# Sheet3.net
KiCad netlist of a schematic drawn in Altium Designer
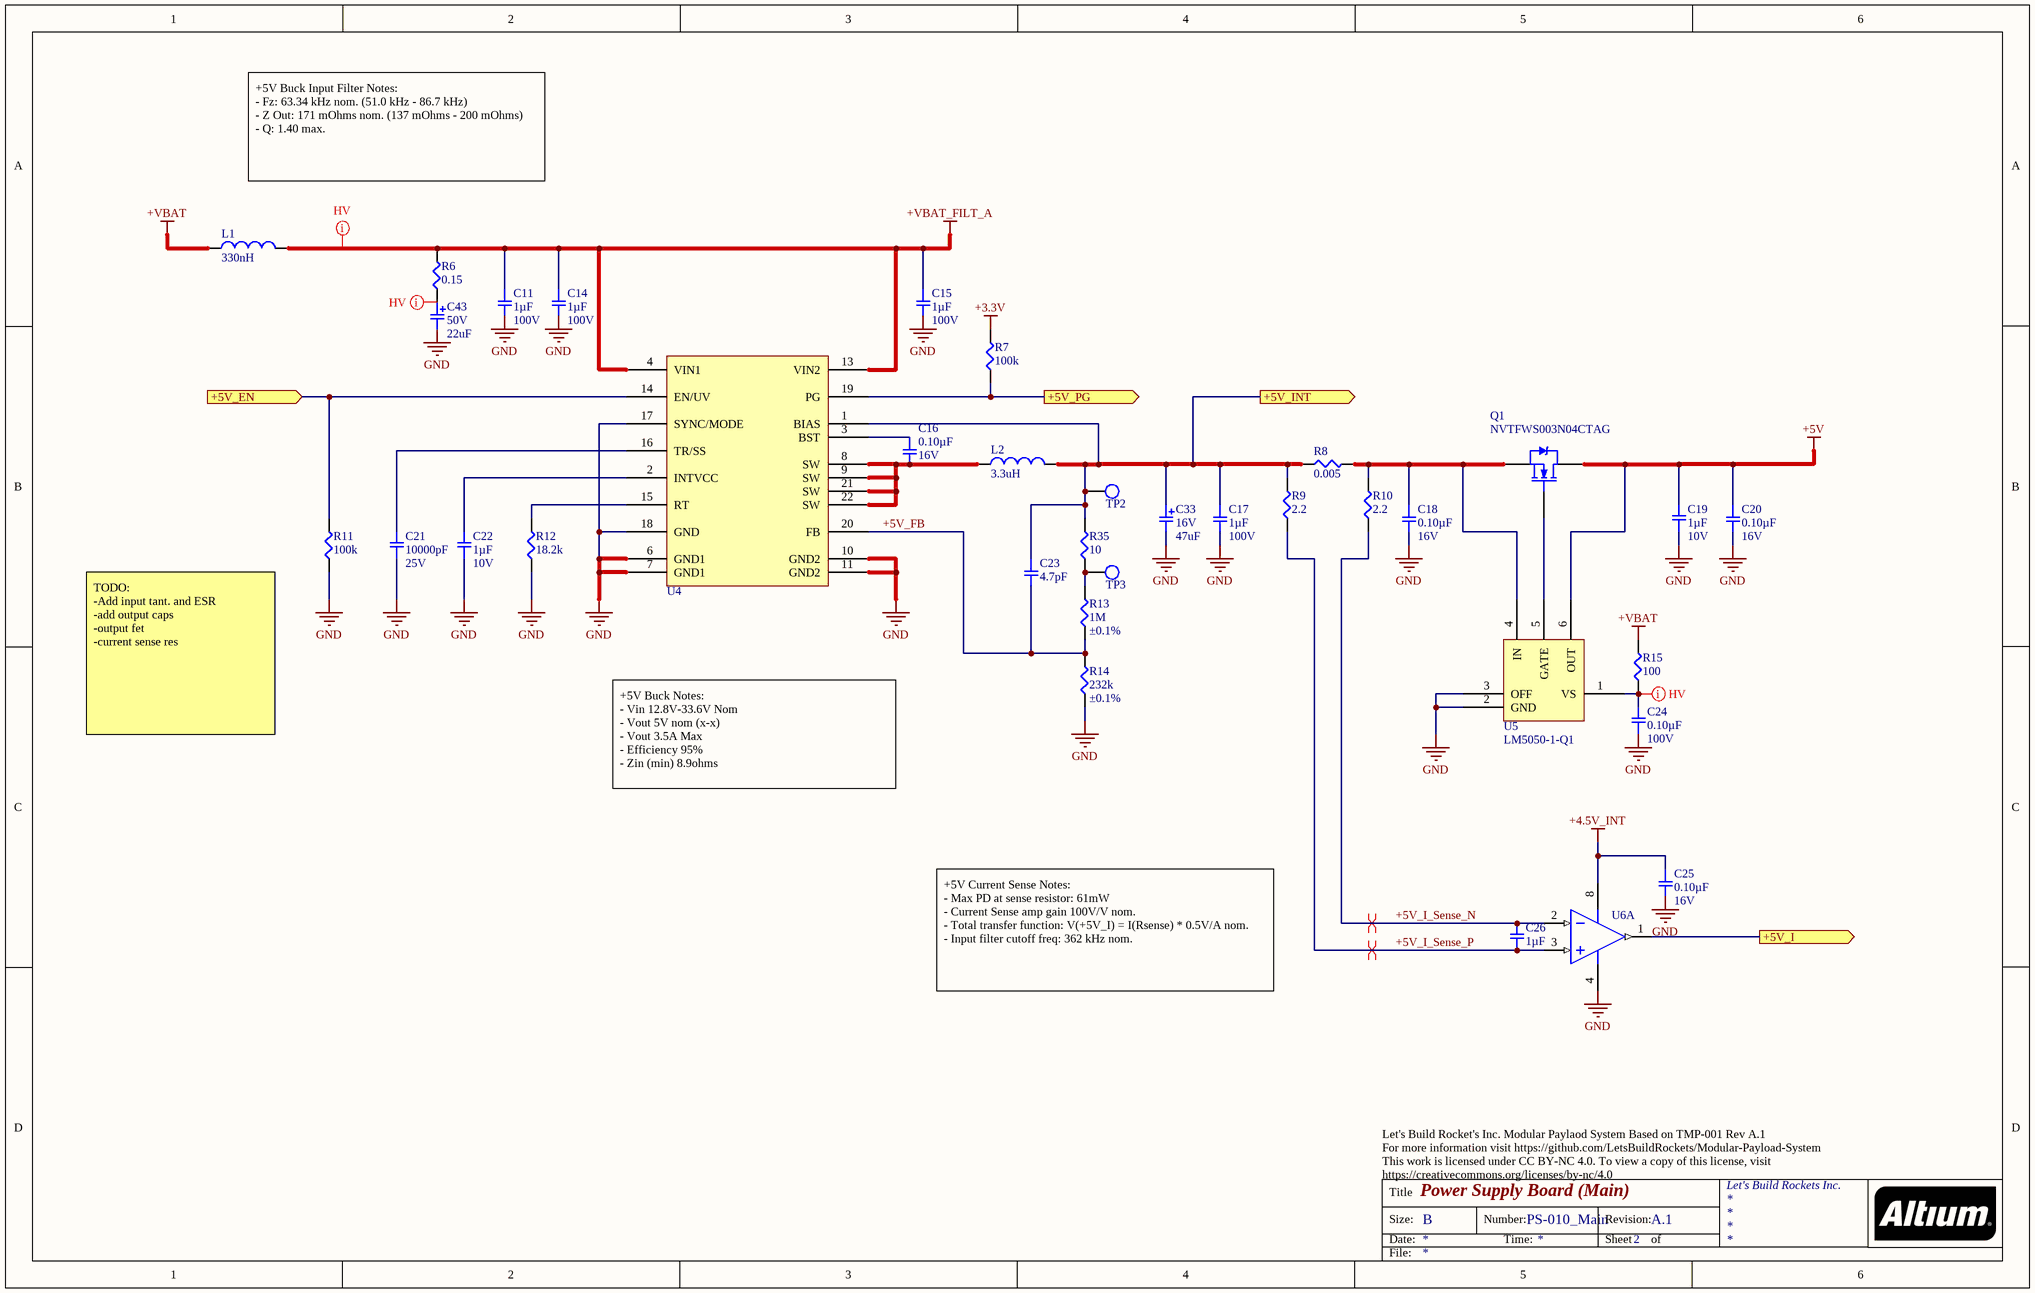
[diagram p0: Sheet3.SchDoc]

(export (version "E")
  (design (tool "Eeschema 10.0.6"))
  (components
    (comp (ref "C11")
      (value "1µF")
      (footprint "SMD-0805C")
      (description "CAP CER 1UF 100V X7S 0805")
      (fields
        (field (name "DIGI-KEY PART NUMBER") "490-10918-1-ND")
        (field (name "PART NUMBER") "GRJ21BC72A105KE11L")
        (field (name "VOLTAGE") "100V")
      )
      (libsource (lib "capacitor_murata_0805") (part "GRJ21BC72A105KE11L"))
    )
    (comp (ref "C14")
      (value "1µF")
      (footprint "SMD-0805C")
      (description "CAP CER 1UF 100V X7S 0805")
      (fields
        (field (name "DIGI-KEY PART NUMBER") "490-10918-1-ND")
        (field (name "PART NUMBER") "GRJ21BC72A105KE11L")
        (field (name "VOLTAGE") "100V")
      )
      (libsource (lib "capacitor_murata_0805") (part "GRJ21BC72A105KE11L"))
    )
    (comp (ref "C15")
      (value "1µF")
      (footprint "SMD-0805C")
      (description "CAP CER 1UF 100V X7S 0805")
      (fields
        (field (name "DIGI-KEY PART NUMBER") "490-10918-1-ND")
        (field (name "PART NUMBER") "GRJ21BC72A105KE11L")
        (field (name "VOLTAGE") "100V")
      )
      (libsource (lib "capacitor_murata_0805") (part "GRJ21BC72A105KE11L"))
    )
    (comp (ref "C16")
      (value "0.10µF")
      (footprint "SMD-0402C")
      (description "CAP CER 0.1UF 16V X7R 0402")
      (fields
        (field (name "DIGI-KEY PART NUMBER") "490-4759-1-ND")
        (field (name "PART NUMBER") "GCM155R71C104KA55D")
        (field (name "VOLTAGE") "16V")
      )
      (libsource (lib "capacitor_murata_0402") (part "GCM155R71C104KA55D"))
    )
    (comp (ref "C17")
      (value "1µF")
      (footprint "SMD-0805C")
      (description "CAP CER 1UF 100V X7S 0805")
      (fields
        (field (name "DIGI-KEY PART NUMBER") "490-10918-1-ND")
        (field (name "PART NUMBER") "GRJ21BC72A105KE11L")
        (field (name "VOLTAGE") "100V")
      )
      (libsource (lib "capacitor_murata_0805") (part "GRJ21BC72A105KE11L"))
    )
    (comp (ref "C18")
      (value "0.10µF")
      (footprint "SMD-0402C")
      (description "CAP CER 0.1UF 16V X7R 0402")
      (fields
        (field (name "DIGI-KEY PART NUMBER") "490-4759-1-ND")
        (field (name "PART NUMBER") "GCM155R71C104KA55D")
        (field (name "VOLTAGE") "16V")
      )
      (libsource (lib "capacitor_murata_0402") (part "GCM155R71C104KA55D"))
    )
    (comp (ref "C19")
      (value "1µF")
      (footprint "SMD-0402C")
      (description "CAP CER 1UF 10V X7S 0402")
      (fields
        (field (name "DIGI-KEY PART NUMBER") "490-13409-1-ND")
        (field (name "PART NUMBER") "GCM155C71A105KE38D")
        (field (name "VOLTAGE") "10V")
      )
      (libsource (lib "capacitor_murata_0402") (part "GCM155C71A105KE38D"))
    )
    (comp (ref "C20")
      (value "0.10µF")
      (footprint "SMD-0402C")
      (description "CAP CER 0.1UF 16V X7R 0402")
      (fields
        (field (name "DIGI-KEY PART NUMBER") "490-4759-1-ND")
        (field (name "PART NUMBER") "GCM155R71C104KA55D")
        (field (name "VOLTAGE") "16V")
      )
      (libsource (lib "capacitor_murata_0402") (part "GCM155R71C104KA55D"))
    )
    (comp (ref "C21")
      (value "10000pF")
      (footprint "SMD-0402C")
      (description "CAP CER 10000PF 25V X7R 0402")
      (fields
        (field (name "DIGI-KEY PART NUMBER") "490-6043-1-ND")
        (field (name "PART NUMBER") "GCM155R71E103KA37D")
        (field (name "VOLTAGE") "25V")
      )
      (libsource (lib "capacitor_murata_0402") (part "GCM155R71E103KA37D"))
    )
    (comp (ref "C22")
      (value "1µF")
      (footprint "SMD-0402C")
      (description "CAP CER 1UF 10V X7S 0402")
      (fields
        (field (name "DIGI-KEY PART NUMBER") "490-13409-1-ND")
        (field (name "PART NUMBER") "GCM155C71A105KE38D")
        (field (name "VOLTAGE") "10V")
      )
      (libsource (lib "capacitor_murata_0402") (part "GCM155C71A105KE38D"))
    )
    (comp (ref "C23")
      (value "4.7pF")
      (footprint "SMD-0402C")
      (description "CAP CER 4.7PF 50V NP0 0402")
      (fields
        (field (name "DIGI-KEY PART NUMBER") "490-12652-1-ND")
        (field (name "PART NUMBER") "GCM1555C1H4R7CA16D")
      )
      (libsource (lib "capacitor_murata_0402") (part "GCM1555C1H4R7CA16D"))
    )
    (comp (ref "C24")
      (value "0.10µF")
      (footprint "SMD-0603C")
      (description "CAP CER 0.1UF 100V X7R 0603")
      (fields
        (field (name "DIGI-KEY PART NUMBER") "490-3285-1-ND")
        (field (name "PART NUMBER") "GRM188R72A104KA35D")
        (field (name "VOLTAGE") "100V")
      )
      (libsource (lib "capacitor_murata_0603") (part "GRM188R72A104KA35D"))
    )
    (comp (ref "C25")
      (value "0.10µF")
      (footprint "SMD-0402C")
      (description "CAP CER 0.1UF 16V X7R 0402")
      (fields
        (field (name "DIGI-KEY PART NUMBER") "490-4759-1-ND")
        (field (name "PART NUMBER") "GCM155R71C104KA55D")
        (field (name "VOLTAGE") "16V")
      )
      (libsource (lib "capacitor_murata_0402") (part "GCM155R71C104KA55D"))
    )
    (comp (ref "C26")
      (value "1µF")
      (footprint "SMD-0402C")
      (description "CAP CER 1UF 10V X7S 0402")
      (fields
        (field (name "DIGI-KEY PART NUMBER") "490-13409-1-ND")
        (field (name "PART NUMBER") "GCM155C71A105KE38D")
      )
      (libsource (lib "capacitor_murata_0402") (part "GCM155C71A105KE38D"))
    )
    (comp (ref "C33")
      (value "47uF")
      (footprint "KEMET W - CAPMP7343X15N")
      (fields (field (name "VOLTAGE") "16V") (field (name "Comment") "T521W476M016ATE045"))
      (libsource (lib "KEMET") (part "T521W476M016ATE045"))
    )
    (comp (ref "C43")
      (value "22uF")
      (footprint "KEMET D - CAPMP7343X31N")
      (fields (field (name "VOLTAGE") "50V") (field (name "Comment") "T521D226M050ATE090"))
      (libsource (lib "KEMET") (part "T521D226M050ATE090"))
    )
    (comp (ref "L1")
      (value "330nH")
      (footprint "INDM4040X21N (XGL4020)")
      (fields (field (name "Comment") "XGL4020-331ME"))
      (libsource (lib "ModularPayload") (part "XGL4020-331ME"))
    )
    (comp (ref "L2")
      (value "3.3uH")
      (footprint "INDM7050X50N (Wurth)")
      (fields (field (name "TOLERANCE") "20%") (field (name "Comment") "744314330"))
      (libsource (lib "ModularPayload") (part "744314330"))
    )
    (comp (ref "Q1")
      (value "NVTFWS003N04CTAG")
      (footprint "DFN065P305X80-8N")
      (libsource (lib "ModularPayload") (part "NVTFWS003N04CTAG"))
    )
    (comp (ref "R6")
      (value "0.15")
      (footprint "SMD-0603-RES")
      (description "RES SMD 0.15 OHM 5% 1/4W 0603")
      (fields (field (name "PART NUMBER") "ERJ-3BSJR15V") (field (name "DIGI-KEY PART NUMBER") "P17248CT-ND"))
      (libsource (lib "Panasonic_ERJ_0603") (part "ERJ-3BSJR15V"))
    )
    (comp (ref "R7")
      (value "100k")
      (footprint "SMD-0402-RES")
      (description "RES SMD 100K OHM 5% 1/10W 0402")
      (fields (field (name "PART NUMBER") "ERJ-2GEJ104X") (field (name "DIGI-KEY PART NUMBER") "P100KJCT-ND"))
      (libsource (lib "Panasonic_ERJ_0402") (part "ERJ-2GEJ104X"))
    )
    (comp (ref "R8")
      (value "0.005")
      (footprint "SMD-0603-RES")
      (description "RES SMD 0.005 OHM 1% 1/4W 0603")
      (fields
        (field (name "PART NUMBER") "ERJ-3LWFR005V")
        (field (name "DIGI-KEY PART NUMBER") "P19182CT-ND")
      )
      (libsource (lib "Panasonic_ERJ_0603") (part "ERJ-3LWFR005V"))
    )
    (comp (ref "R9")
      (value "2.2")
      (footprint "SMD-0603-RES")
      (description "RES SMD 2.2 OHM 1% 1/10W 0603")
      (fields (field (name "PART NUMBER") "ERJ-3RQF2R2V") (field (name "DIGI-KEY PART NUMBER") "P2.2AJCT-ND"))
      (libsource (lib "Panasonic_ERJ_0603") (part "ERJ-3RQF2R2V"))
    )
    (comp (ref "R10")
      (value "2.2")
      (footprint "SMD-0603-RES")
      (description "RES SMD 2.2 OHM 1% 1/10W 0603")
      (fields (field (name "PART NUMBER") "ERJ-3RQF2R2V") (field (name "DIGI-KEY PART NUMBER") "P2.2AJCT-ND"))
      (libsource (lib "Panasonic_ERJ_0603") (part "ERJ-3RQF2R2V"))
    )
    (comp (ref "R11")
      (value "100k")
      (footprint "SMD-0402-RES")
      (description "RES SMD 100K OHM 5% 1/10W 0402")
      (fields (field (name "PART NUMBER") "ERJ-2GEJ104X") (field (name "DIGI-KEY PART NUMBER") "P100KJCT-ND"))
      (libsource (lib "Panasonic_ERJ_0402") (part "ERJ-2GEJ104X"))
    )
    (comp (ref "R12")
      (value "18.2k")
      (footprint "SMD-0402-RES")
      (description "RES SMD 18.2K OHM 1% 1/10W 0402")
      (fields
        (field (name "PART NUMBER") "ERJ-2RKF1822X")
        (field (name "DIGI-KEY PART NUMBER") "P18.2KLCT-ND")
      )
      (libsource (lib "Panasonic_ERJ_0402") (part "ERJ-2RKF1822X"))
    )
    (comp (ref "R13")
      (value "1M")
      (footprint "SMD-0805-RES")
      (description "RES SMD 1M OHM 0.1% 1/4W 0805")
      (fields
        (field (name "PART NUMBER") "ERJ-PB6B1004V")
        (field (name "DIGI-KEY PART NUMBER") "P20936CT-ND")
        (field (name "TOLERANCE") "±0.1%")
      )
      (libsource (lib "Panasonic_ERJ_0805") (part "ERJ-PB6B1004V"))
    )
    (comp (ref "R14")
      (value "232k")
      (footprint "SMD-0805-RES")
      (description "RES SMD 232k OHM 0.1% 1/4W 0805")
      (fields
        (field (name "PART NUMBER") "ERJ-PB6B2323V")
        (field (name "DIGI-KEY PART NUMBER") "P20861CT-ND")
        (field (name "TOLERANCE") "±0.1%")
      )
      (libsource (lib "Panasonic_ERJ_0805") (part "ERJ-PB6B2323V"))
    )
    (comp (ref "R15")
      (value "100")
      (footprint "SMD-0402-RES")
      (description "RES SMD 100 OHM 5% 1/10W 0402")
      (fields (field (name "PART NUMBER") "ERJ-2GEJ101X") (field (name "DIGI-KEY PART NUMBER") "P100JCT-ND"))
      (libsource (lib "Panasonic_ERJ_0402") (part "ERJ-2GEJ101X"))
    )
    (comp (ref "R35")
      (value "10")
      (footprint "SMD-0402-RES")
      (description "RES SMD 10 OHM 5% 1/10W 0402")
      (fields (field (name "PART NUMBER") "ERJ-2GEJ100X") (field (name "DIGI-KEY PART NUMBER") "P10JCT-ND"))
      (libsource (lib "Panasonic_ERJ_0402") (part "ERJ-2GEJ100X"))
    )
    (comp (ref "TP2") (value "TP") (footprint "TP_SMD_40") (libsource (lib "TP") (part "TP")))
    (comp (ref "TP3") (value "TP") (footprint "TP_SMD_40") (libsource (lib "TP") (part "TP")))
    (comp (ref "U4")
      (value "LT8640")
      (footprint "QFN50P300X400X80_HS-21N (LT8640)")
      (libsource (lib "ModularPayload") (part "LT8640"))
    )
    (comp (ref "U5")
      (value "LM5050-1-Q1")
      (footprint "SOT95P280X110-6N")
      (libsource (lib "ModularPayload") (part "LM5050-1-Q1"))
    )
    (comp (ref "U6")
      (value "INA2180A3IDGKT")
      (footprint "TSOP65P490X110-8N")
      (libsource (lib "ModularPayload") (part "INA2180A3IDGKT"))
    )
  )
  (nets
    (net (code "1") (name "+3.3V") (class "Default")
      (node (ref "R7") (pin "2") (pinfunction "2_2") (pintype "passive"))
    )
    (net (code "2") (name "+4.5V_INT") (class "Default")
      (node (ref "C25") (pin "1") (pinfunction "1_1") (pintype "passive"))
      (node (ref "U6") (pin "8") (pinfunction "VS_8") (pintype "power_in"))
    )
    (net (code "3") (name "+5V") (class "Default")
      (node (ref "C19") (pin "2") (pinfunction "2_2") (pintype "passive"))
      (node (ref "C20") (pin "1") (pinfunction "1_1") (pintype "passive"))
      (node (ref "Q1") (pin "D") (pinfunction "D_D") (pintype "passive"))
      (node (ref "U5") (pin "6") (pinfunction "OUT_6") (pintype "passive"))
    )
    (net (code "4") (name "+VBAT") (class "Default")
      (node (ref "L1") (pin "1") (pinfunction "1_1") (pintype "passive"))
      (node (ref "R15") (pin "2") (pinfunction "2_2") (pintype "passive"))
    )
    (net (code "5") (name "+VBAT_FILT_A") (class "Default")
      (node (ref "C11") (pin "1") (pinfunction "1_1") (pintype "passive"))
      (node (ref "C14") (pin "1") (pinfunction "1_1") (pintype "passive"))
      (node (ref "C15") (pin "1") (pinfunction "1_1") (pintype "passive"))
      (node (ref "L1") (pin "2") (pinfunction "2_2") (pintype "passive"))
      (node (ref "R6") (pin "2") (pinfunction "2_2") (pintype "passive"))
      (node (ref "U4") (pin "13") (pinfunction "VIN2_13") (pintype "passive"))
      (node (ref "U4") (pin "4") (pinfunction "VIN1_4") (pintype "passive"))
    )
    (net (code "6") (name "/+5V_EN") (class "Default")
      (node (ref "R11") (pin "2") (pinfunction "2_2") (pintype "passive"))
      (node (ref "U4") (pin "14") (pinfunction "EN/UV_14") (pintype "passive"))
    )
    (net (code "7") (name "/+5V_FB") (class "Default")
      (node (ref "C23") (pin "2") (pinfunction "2_2") (pintype "passive"))
      (node (ref "R13") (pin "1") (pinfunction "1_1") (pintype "passive"))
      (node (ref "R14") (pin "2") (pinfunction "2_2") (pintype "passive"))
      (node (ref "U4") (pin "20") (pinfunction "FB_20") (pintype "passive"))
    )
    (net (code "8") (name "/+5V_I") (class "Default")
      (node (ref "U6") (pin "1") (pinfunction "OUT1_1") (pintype "output"))
    )
    (net (code "9") (name "/+5V_INT") (class "Default")
      (node (ref "C17") (pin "1") (pinfunction "1_1") (pintype "passive"))
      (node (ref "C23") (pin "1") (pinfunction "1_1") (pintype "passive"))
      (node (ref "C33") (pin "1") (pinfunction "1_1") (pintype "passive"))
      (node (ref "L2") (pin "2") (pinfunction "2_2") (pintype "passive"))
      (node (ref "R35") (pin "2") (pinfunction "2_2") (pintype "passive"))
      (node (ref "R8") (pin "1") (pinfunction "1_1") (pintype "passive"))
      (node (ref "R9") (pin "2") (pinfunction "2_2") (pintype "passive"))
      (node (ref "TP2") (pin "1") (pintype "passive"))
      (node (ref "U4") (pin "1") (pinfunction "BIAS_1") (pintype "passive"))
    )
    (net (code "10") (name "/+5V_I_Sense_N") (class "Default")
      (node (ref "C26") (pin "2") (pinfunction "2_2") (pintype "passive"))
      (node (ref "R10") (pin "1") (pinfunction "1_1") (pintype "passive"))
      (node (ref "U6") (pin "2") (pinfunction "IN-1_2") (pintype "input"))
    )
    (net (code "11") (name "/+5V_I_Sense_P") (class "Default")
      (node (ref "C26") (pin "1") (pinfunction "1_1") (pintype "passive"))
      (node (ref "R9") (pin "1") (pinfunction "1_1") (pintype "passive"))
      (node (ref "U6") (pin "3") (pinfunction "IN+1_3") (pintype "input"))
    )
    (net (code "12") (name "/+5V_PG") (class "Default")
      (node (ref "R7") (pin "1") (pinfunction "1_1") (pintype "passive"))
      (node (ref "U4") (pin "19") (pinfunction "PG_19") (pintype "passive"))
    )
    (net (code "13") (name "GND") (class "Default")
      (node (ref "C11") (pin "2") (pinfunction "2_2") (pintype "passive"))
      (node (ref "C14") (pin "2") (pinfunction "2_2") (pintype "passive"))
      (node (ref "C15") (pin "2") (pinfunction "2_2") (pintype "passive"))
      (node (ref "C17") (pin "2") (pinfunction "2_2") (pintype "passive"))
      (node (ref "C18") (pin "2") (pinfunction "2_2") (pintype "passive"))
      (node (ref "C19") (pin "1") (pinfunction "1_1") (pintype "passive"))
      (node (ref "C20") (pin "2") (pinfunction "2_2") (pintype "passive"))
      (node (ref "C21") (pin "1") (pinfunction "1_1") (pintype "passive"))
      (node (ref "C22") (pin "1") (pinfunction "1_1") (pintype "passive"))
      (node (ref "C24") (pin "1") (pinfunction "1_1") (pintype "passive"))
      (node (ref "C25") (pin "2") (pinfunction "2_2") (pintype "passive"))
      (node (ref "C33") (pin "2") (pinfunction "2_2") (pintype "passive"))
      (node (ref "C43") (pin "2") (pinfunction "2_2") (pintype "passive"))
      (node (ref "R11") (pin "1") (pinfunction "1_1") (pintype "passive"))
      (node (ref "R12") (pin "1") (pinfunction "1_1") (pintype "passive"))
      (node (ref "R14") (pin "1") (pinfunction "1_1") (pintype "passive"))
      (node (ref "U4") (pin "10") (pinfunction "GND2_10") (pintype "passive"))
      (node (ref "U4") (pin "11") (pinfunction "GND2_11") (pintype "passive"))
      (node (ref "U4") (pin "17") (pinfunction "SYNC/MODE_17") (pintype "passive"))
      (node (ref "U4") (pin "18") (pinfunction "GND_18") (pintype "passive"))
      (node (ref "U4") (pin "6") (pinfunction "GND1_6") (pintype "passive"))
      (node (ref "U4") (pin "7") (pinfunction "GND1_7") (pintype "passive"))
      (node (ref "U5") (pin "2") (pinfunction "GND_2") (pintype "passive"))
      (node (ref "U5") (pin "3") (pinfunction "OFF_3") (pintype "passive"))
      (node (ref "U6") (pin "4") (pinfunction "GND_4") (pintype "power_in"))
    )
    (net (code "14") (name "Net-(C16-Pad2)") (class "Default")
      (node (ref "C16") (pin "2") (pinfunction "2_2") (pintype "passive"))
      (node (ref "L2") (pin "1") (pinfunction "1_1") (pintype "passive"))
      (node (ref "U4") (pin "21") (pinfunction "SW_21") (pintype "passive"))
      (node (ref "U4") (pin "22") (pinfunction "SW_22") (pintype "passive"))
      (node (ref "U4") (pin "8") (pinfunction "SW_8") (pintype "passive"))
      (node (ref "U4") (pin "9") (pinfunction "SW_9") (pintype "passive"))
    )
    (net (code "15") (name "Net-(C43-Pad1)") (class "Default")
      (node (ref "C43") (pin "1") (pinfunction "1_1") (pintype "passive"))
      (node (ref "R6") (pin "1") (pinfunction "1_1") (pintype "passive"))
    )
    (net (code "16") (name "Net-(R13-Pad2)") (class "Default")
      (node (ref "R13") (pin "2") (pinfunction "2_2") (pintype "passive"))
      (node (ref "R35") (pin "1") (pinfunction "1_1") (pintype "passive"))
      (node (ref "TP3") (pin "1") (pintype "passive"))
    )
    (net (code "17") (name "Net-(U4-BST)") (class "Default")
      (node (ref "C16") (pin "1") (pinfunction "1_1") (pintype "passive"))
      (node (ref "U4") (pin "3") (pinfunction "BST_3") (pintype "passive"))
    )
    (net (code "18") (name "Net-(U4-INTVCC)") (class "Default")
      (node (ref "C22") (pin "2") (pinfunction "2_2") (pintype "passive"))
      (node (ref "U4") (pin "2") (pinfunction "INTVCC_2") (pintype "passive"))
    )
    (net (code "19") (name "Net-(U4-RT)") (class "Default")
      (node (ref "R12") (pin "2") (pinfunction "2_2") (pintype "passive"))
      (node (ref "U4") (pin "15") (pinfunction "RT_15") (pintype "passive"))
    )
    (net (code "20") (name "Net-(U4-TR{slash}SS)") (class "Default")
      (node (ref "C21") (pin "2") (pinfunction "2_2") (pintype "passive"))
      (node (ref "U4") (pin "16") (pinfunction "TR/SS_16") (pintype "passive"))
    )
    (net (code "21") (name "Net-(U5-GATE)") (class "Default")
      (node (ref "Q1") (pin "G") (pinfunction "G_G") (pintype "passive"))
      (node (ref "U5") (pin "5") (pinfunction "GATE_5") (pintype "passive"))
    )
    (net (code "22") (name "Net-(U5-IN)") (class "Default")
      (node (ref "C18") (pin "1") (pinfunction "1_1") (pintype "passive"))
      (node (ref "Q1") (pin "S") (pinfunction "S_S") (pintype "passive"))
      (node (ref "R10") (pin "2") (pinfunction "2_2") (pintype "passive"))
      (node (ref "R8") (pin "2") (pinfunction "2_2") (pintype "passive"))
      (node (ref "U5") (pin "4") (pinfunction "IN_4") (pintype "passive"))
    )
    (net (code "23") (name "Net-(U5-VS)") (class "Default")
      (node (ref "C24") (pin "2") (pinfunction "2_2") (pintype "passive"))
      (node (ref "R15") (pin "1") (pinfunction "1_1") (pintype "passive"))
      (node (ref "U5") (pin "1") (pinfunction "VS_1") (pintype "passive"))
    )
  )
)
